# reverb2.net
KiCad netlist of a schematic drawn in EAGLE
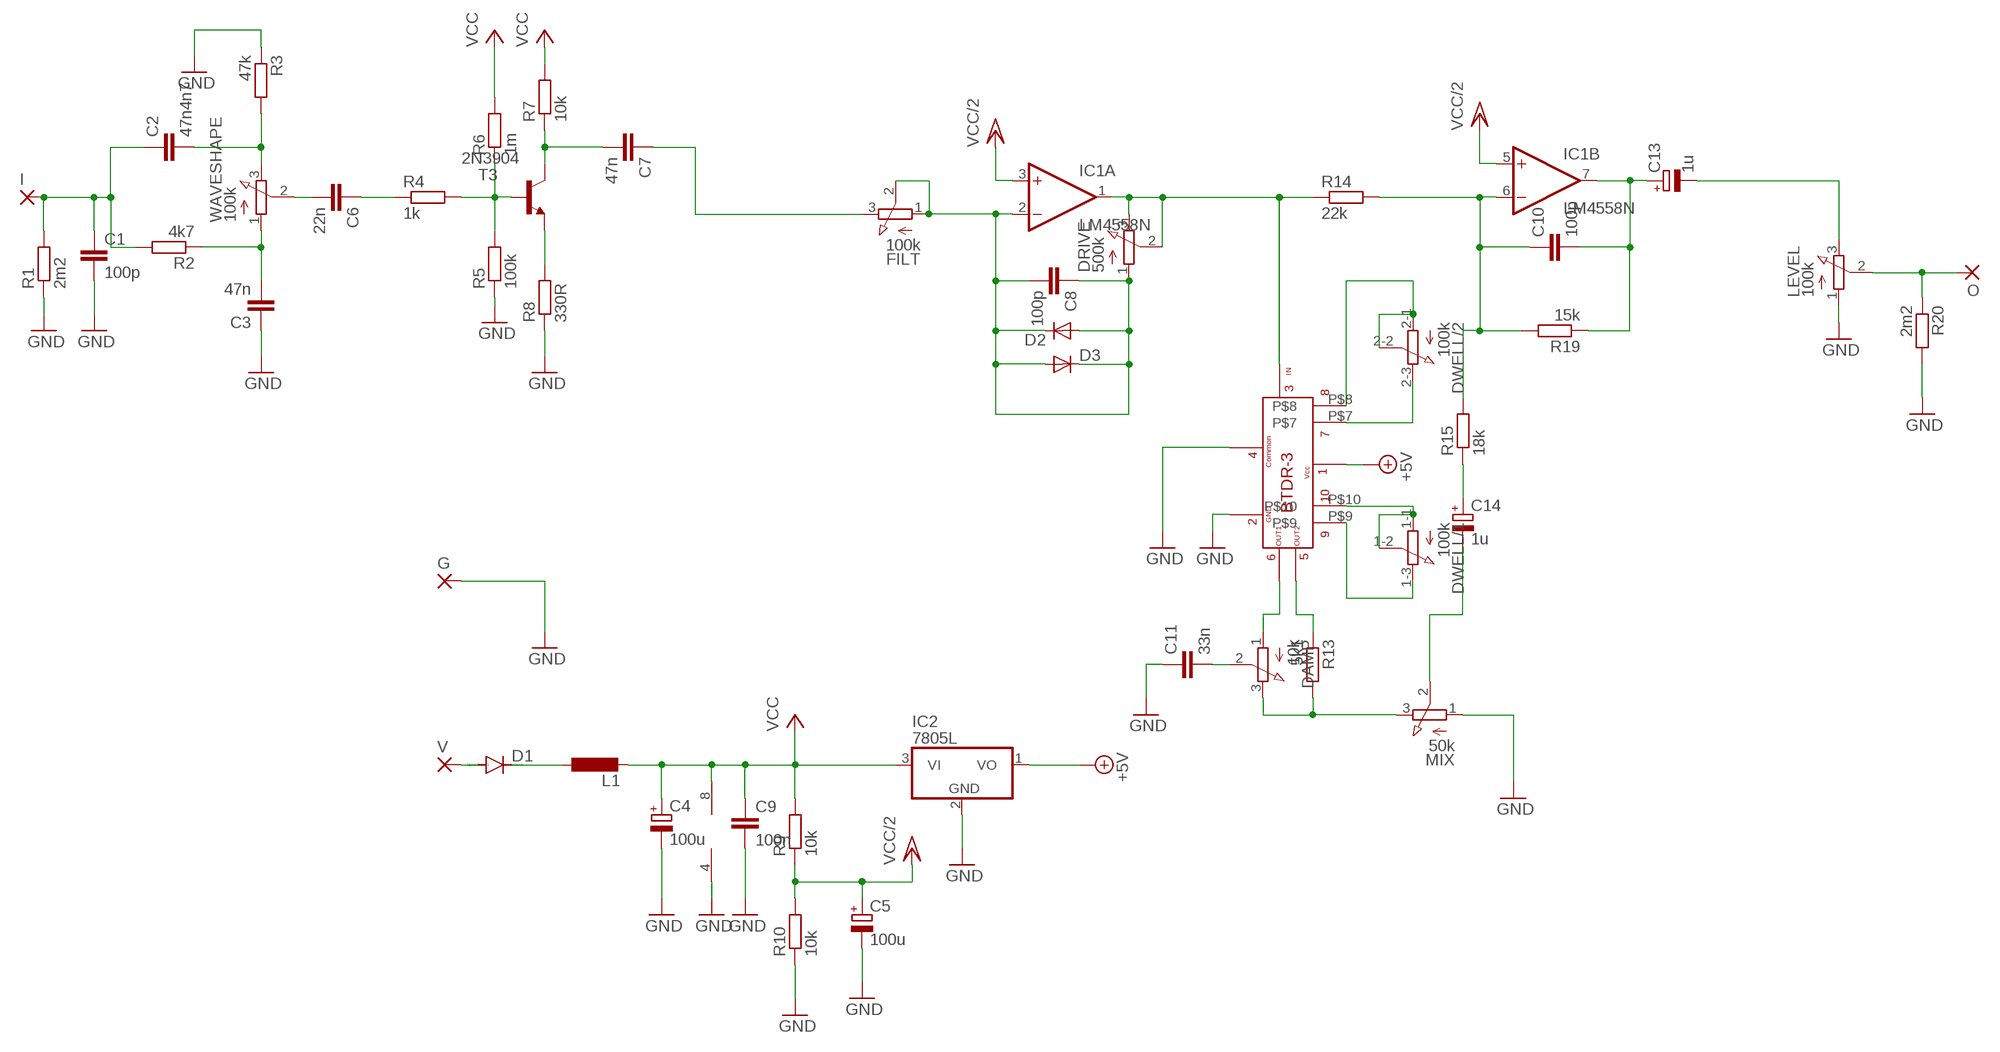
[diagram p0: schematic, sheet 1]

(export (version "E")
  (design (tool "Eeschema 10.0.6"))
  (components
    (comp (ref "C1")
      (value "100p")
      (footprint "eagle-import:S5MMHEXCAP")
      (libsource (lib "eagle-import") (part "C5/2.5"))
    )
    (comp (ref "C2")
      (value "47n4n7")
      (footprint "eagle-import:S5MMHEXCAP")
      (libsource (lib "eagle-import") (part "C5/2.5"))
    )
    (comp (ref "C3")
      (value "47n")
      (footprint "eagle-import:S5MMHEXCAP")
      (libsource (lib "eagle-import") (part "C5/2.5"))
    )
    (comp (ref "C4")
      (value "100u")
      (footprint "eagle-import:E2,5-7")
      (libsource (lib "eagle-import") (part "CPOL-EUE2.5-7"))
    )
    (comp (ref "C5")
      (value "100u")
      (footprint "eagle-import:E2,5-7")
      (libsource (lib "eagle-import") (part "CPOL-EUE2.5-7"))
    )
    (comp (ref "C6")
      (value "22n")
      (footprint "eagle-import:S5MMHEXCAP")
      (libsource (lib "eagle-import") (part "C5/2.5"))
    )
    (comp (ref "C7")
      (value "47n")
      (footprint "eagle-import:S5MMHEXCAP")
      (libsource (lib "eagle-import") (part "C5/2.5"))
    )
    (comp (ref "C8")
      (value "100p")
      (footprint "eagle-import:S5MMHEXCAP")
      (libsource (lib "eagle-import") (part "C5/2.5"))
    )
    (comp (ref "C9")
      (value "100n")
      (footprint "eagle-import:S5MMHEXCAP")
      (libsource (lib "eagle-import") (part "C5/2.5"))
    )
    (comp (ref "C10")
      (value "100p")
      (footprint "eagle-import:S5MMHEXCAP")
      (libsource (lib "eagle-import") (part "C5/2.5"))
    )
    (comp (ref "C11")
      (value "33n")
      (footprint "eagle-import:S5MMHEXCAP")
      (libsource (lib "eagle-import") (part "C5/2.5"))
    )
    (comp (ref "C13")
      (value "1u")
      (footprint "eagle-import:E2-4")
      (libsource (lib "eagle-import") (part "CPOL-EUE2-4"))
    )
    (comp (ref "C14")
      (value "1u")
      (footprint "eagle-import:E2-4")
      (libsource (lib "eagle-import") (part "CPOL-EUE2-4"))
    )
    (comp (ref "D1")
      (value "1N4148DO35-7")
      (footprint "eagle-import:DO35-7")
      (libsource (lib "eagle-import") (part "1N4148DO35-7"))
    )
    (comp (ref "D2")
      (value "SMALL_DIODEDO35-7")
      (footprint "eagle-import:DO35-7")
      (libsource (lib "eagle-import") (part "SMALL_DIODEDO35-7"))
    )
    (comp (ref "D3")
      (value "SMALL_DIODEDO35-7")
      (footprint "eagle-import:DO35-7")
      (libsource (lib "eagle-import") (part "SMALL_DIODEDO35-7"))
    )
    (comp (ref "DAMP")
      (value "10k")
      (footprint "eagle-import:3RP_1610N")
      (libsource (lib "eagle-import") (part "HEXPOT1"))
    )
    (comp (ref "DRIVE")
      (value "500k")
      (footprint "eagle-import:3RP_1610N")
      (libsource (lib "eagle-import") (part "HEXPOT1"))
    )
    (comp (ref "DWELL")
      (value "100k")
      (footprint "eagle-import:3RP_1610G")
      (libsource (lib "eagle-import") (part "3RP/1610G"))
    )
    (comp (ref "FILT")
      (value "100k")
      (footprint "eagle-import:3RP_1610N")
      (libsource (lib "eagle-import") (part "HEXPOT1"))
    )
    (comp (ref "G")
      (value "WIREPAD1,6/0,9")
      (footprint "eagle-import:1,6_0,9")
      (libsource (lib "eagle-import") (part "WIREPAD1,6/0,9"))
    )
    (comp (ref "I")
      (value "WIREPAD1,6/0,9")
      (footprint "eagle-import:1,6_0,9")
      (libsource (lib "eagle-import") (part "WIREPAD1,6/0,9"))
    )
    (comp (ref "IC1")
      (value "LM4558N")
      (footprint "eagle-import:DIL08")
      (libsource (lib "eagle-import") (part "4558NLM"))
    )
    (comp (ref "IC2")
      (value "7805L")
      (footprint "eagle-import:TO92")
      (libsource (lib "eagle-import") (part "78L05"))
    )
    (comp (ref "L1")
      (value "L-EU0204/7")
      (footprint "eagle-import:0204_7")
      (libsource (lib "eagle-import") (part "L-EU0204/7"))
    )
    (comp (ref "LEVEL")
      (value "100k")
      (footprint "eagle-import:3RP_1610N")
      (libsource (lib "eagle-import") (part "HEXPOT1"))
    )
    (comp (ref "MIX")
      (value "50k")
      (footprint "eagle-import:3RP_1610N")
      (libsource (lib "eagle-import") (part "HEXPOT1"))
    )
    (comp (ref "O")
      (value "WIREPAD1,6/0,9")
      (footprint "eagle-import:1,6_0,9")
      (libsource (lib "eagle-import") (part "WIREPAD1,6/0,9"))
    )
    (comp (ref "R1")
      (value "2m2")
      (footprint "eagle-import:0207_7")
      (libsource (lib "eagle-import") (part "R-EU_0207/7"))
    )
    (comp (ref "R2")
      (value "4k7")
      (footprint "eagle-import:0207_7")
      (libsource (lib "eagle-import") (part "R-EU_0207/7"))
    )
    (comp (ref "R3")
      (value "47k")
      (footprint "eagle-import:0207_7")
      (libsource (lib "eagle-import") (part "R-EU_0207/7"))
    )
    (comp (ref "R4")
      (value "1k")
      (footprint "eagle-import:0207_7")
      (libsource (lib "eagle-import") (part "R-EU_0207/7"))
    )
    (comp (ref "R5")
      (value "100k")
      (footprint "eagle-import:0207_7")
      (libsource (lib "eagle-import") (part "R-EU_0207/7"))
    )
    (comp (ref "R6")
      (value "1m")
      (footprint "eagle-import:0207_7")
      (libsource (lib "eagle-import") (part "R-EU_0207/7"))
    )
    (comp (ref "R7")
      (value "10k")
      (footprint "eagle-import:0207_7")
      (libsource (lib "eagle-import") (part "R-EU_0207/7"))
    )
    (comp (ref "R8")
      (value "330R")
      (footprint "eagle-import:0207_7")
      (libsource (lib "eagle-import") (part "R-EU_0207/7"))
    )
    (comp (ref "R9")
      (value "10k")
      (footprint "eagle-import:0207_7")
      (libsource (lib "eagle-import") (part "R-EU_0207/7"))
    )
    (comp (ref "R10")
      (value "10k")
      (footprint "eagle-import:0207_7")
      (libsource (lib "eagle-import") (part "R-EU_0207/7"))
    )
    (comp (ref "R13")
      (value "5k1")
      (footprint "eagle-import:0207_7")
      (libsource (lib "eagle-import") (part "R-EU_0207/7"))
    )
    (comp (ref "R14")
      (value "22k")
      (footprint "eagle-import:0207_7")
      (libsource (lib "eagle-import") (part "R-EU_0207/7"))
    )
    (comp (ref "R15")
      (value "18k")
      (footprint "eagle-import:0207_7")
      (libsource (lib "eagle-import") (part "R-EU_0207/7"))
    )
    (comp (ref "R19")
      (value "15k")
      (footprint "eagle-import:0207_7")
      (libsource (lib "eagle-import") (part "R-EU_0207/7"))
    )
    (comp (ref "R20")
      (value "2m2")
      (footprint "eagle-import:0207_7")
      (libsource (lib "eagle-import") (part "R-EU_0207/7"))
    )
    (comp (ref "T3")
      (value "2N3904")
      (footprint "eagle-import:TO92")
      (libsource (lib "eagle-import") (part "2N3904"))
    )
    (comp (ref "U$2")
      (value "BTDR-3")
      (footprint "eagle-import:BTDR3")
      (libsource (lib "eagle-import") (part "BTDR-3"))
    )
    (comp (ref "V")
      (value "WIREPAD1,6/0,9")
      (footprint "eagle-import:1,6_0,9")
      (libsource (lib "eagle-import") (part "WIREPAD1,6/0,9"))
    )
    (comp (ref "WAVESHAPE")
      (value "100k")
      (footprint "eagle-import:3RP_1610N")
      (libsource (lib "eagle-import") (part "HEXPOT1"))
    )
  )
  (nets
    (net (code "1") (name "+5V") (class "Default")
      (node (ref "IC2") (pin "1") (pinfunction "VO_1") (pintype "passive"))
      (node (ref "U$2") (pin "P$1") (pinfunction "P$1_P$1") (pintype "bidirectional"))
    )
    (net (code "2") (name "GND") (class "Default")
      (node (ref "C1") (pin "2") (pinfunction "2_2") (pintype "passive"))
      (node (ref "C11") (pin "1") (pinfunction "1_1") (pintype "passive"))
      (node (ref "C3") (pin "1") (pinfunction "1_1") (pintype "passive"))
      (node (ref "C4") (pin "-") (pinfunction "-_-") (pintype "passive"))
      (node (ref "C5") (pin "-") (pinfunction "-_-") (pintype "passive"))
      (node (ref "C9") (pin "2") (pinfunction "2_2") (pintype "passive"))
      (node (ref "G") (pin "1") (pinfunction "P_1") (pintype "passive"))
      (node (ref "IC1") (pin "4") (pinfunction "V-_4") (pintype "power_in"))
      (node (ref "IC2") (pin "2") (pinfunction "GND_2") (pintype "passive"))
      (node (ref "LEVEL") (pin "1") (pinfunction "A_1") (pintype "passive"))
      (node (ref "MIX") (pin "1") (pinfunction "A_1") (pintype "passive"))
      (node (ref "R1") (pin "1") (pinfunction "1_1") (pintype "passive"))
      (node (ref "R10") (pin "1") (pinfunction "1_1") (pintype "passive"))
      (node (ref "R20") (pin "2") (pinfunction "2_2") (pintype "passive"))
      (node (ref "R3") (pin "1") (pinfunction "1_1") (pintype "passive"))
      (node (ref "R5") (pin "1") (pinfunction "1_1") (pintype "passive"))
      (node (ref "R8") (pin "1") (pinfunction "1_1") (pintype "passive"))
      (node (ref "U$2") (pin "P$2") (pinfunction "P$2_P$2") (pintype "bidirectional"))
      (node (ref "U$2") (pin "P$4") (pinfunction "P$4_P$4") (pintype "bidirectional"))
    )
    (net (code "3") (name "Net-(C6-Pad1)") (class "Default")
      (node (ref "C6") (pin "1") (pinfunction "1_1") (pintype "passive"))
      (node (ref "R4") (pin "1") (pinfunction "1_1") (pintype "passive"))
    )
    (net (code "4") (name "Net-(C14-Pad+)") (class "Default")
      (node (ref "C14") (pin "+") (pinfunction "+_+") (pintype "passive"))
      (node (ref "R15") (pin "1") (pinfunction "1_1") (pintype "passive"))
    )
    (net (code "5") (name "Net-(D1-PadC)") (class "Default")
      (node (ref "D1") (pin "C") (pinfunction "C_C") (pintype "passive"))
      (node (ref "L1") (pin "1") (pinfunction "1_1") (pintype "passive"))
    )
    (net (code "6") (name "Net-(DAMP-A)") (class "Default")
      (node (ref "DAMP") (pin "1") (pinfunction "A_1") (pintype "passive"))
      (node (ref "U$2") (pin "P$6") (pinfunction "P$6_P$6") (pintype "bidirectional"))
    )
    (net (code "7") (name "Net-(DAMP-E)") (class "Default")
      (node (ref "DAMP") (pin "3") (pinfunction "E_3") (pintype "passive"))
      (node (ref "MIX") (pin "3") (pinfunction "E_3") (pintype "passive"))
      (node (ref "R13") (pin "2") (pinfunction "2_2") (pintype "passive"))
    )
    (net (code "8") (name "Net-(DAMP-S)") (class "Default")
      (node (ref "C11") (pin "2") (pinfunction "2_2") (pintype "passive"))
      (node (ref "DAMP") (pin "2") (pinfunction "S_2") (pintype "passive"))
    )
    (net (code "9") (name "Net-(DRIVE-A)") (class "Default")
      (node (ref "C8") (pin "1") (pinfunction "1_1") (pintype "passive"))
      (node (ref "C8") (pin "2") (pinfunction "2_2") (pintype "passive"))
      (node (ref "D2") (pin "A") (pinfunction "A_A") (pintype "passive"))
      (node (ref "D2") (pin "C") (pinfunction "C_C") (pintype "passive"))
      (node (ref "D3") (pin "A") (pinfunction "A_A") (pintype "passive"))
      (node (ref "D3") (pin "C") (pinfunction "C_C") (pintype "passive"))
      (node (ref "DRIVE") (pin "1") (pinfunction "A_1") (pintype "passive"))
      (node (ref "FILT") (pin "1") (pinfunction "A_1") (pintype "passive"))
      (node (ref "FILT") (pin "2") (pinfunction "S_2") (pintype "passive"))
      (node (ref "IC1") (pin "2") (pinfunction "-IN_2") (pintype "input"))
    )
    (net (code "10") (name "Net-(DRIVE-E)") (class "Default")
      (node (ref "DRIVE") (pin "2") (pinfunction "S_2") (pintype "passive"))
      (node (ref "DRIVE") (pin "3") (pinfunction "E_3") (pintype "passive"))
      (node (ref "IC1") (pin "1") (pinfunction "OUT_1") (pintype "output"))
      (node (ref "R14") (pin "1") (pinfunction "1_1") (pintype "passive"))
      (node (ref "U$2") (pin "P$3") (pinfunction "P$3_P$3") (pintype "bidirectional"))
    )
    (net (code "11") (name "Net-(DWELLA-A)") (class "Default")
      (node (ref "DWELL") (pin "1-1") (pinfunction "A_1-1") (pintype "passive"))
      (node (ref "DWELL") (pin "1-2") (pinfunction "S_1-2") (pintype "passive"))
      (node (ref "U$2") (pin "P$10") (pinfunction "P$10_P$10") (pintype "bidirectional"))
    )
    (net (code "12") (name "Net-(DWELLA-E)") (class "Default")
      (node (ref "DWELL") (pin "1-3") (pinfunction "E_1-3") (pintype "passive"))
      (node (ref "U$2") (pin "P$9") (pinfunction "P$9_P$9") (pintype "bidirectional"))
    )
    (net (code "13") (name "Net-(DWELLB-A)") (class "Default")
      (node (ref "DWELL") (pin "2-1") (pinfunction "A_2-1") (pintype "passive"))
      (node (ref "DWELL") (pin "2-2") (pinfunction "S_2-2") (pintype "passive"))
      (node (ref "U$2") (pin "P$8") (pinfunction "P$8_P$8") (pintype "bidirectional"))
    )
    (net (code "14") (name "Net-(DWELLB-E)") (class "Default")
      (node (ref "DWELL") (pin "2-3") (pinfunction "E_2-3") (pintype "passive"))
      (node (ref "U$2") (pin "P$7") (pinfunction "P$7_P$7") (pintype "bidirectional"))
    )
    (net (code "15") (name "Net-(FILT-E)") (class "Default")
      (node (ref "C7") (pin "1") (pinfunction "1_1") (pintype "passive"))
      (node (ref "FILT") (pin "3") (pinfunction "E_3") (pintype "passive"))
    )
    (net (code "16") (name "Net-(I-P)") (class "Default")
      (node (ref "C1") (pin "1") (pinfunction "1_1") (pintype "passive"))
      (node (ref "C2") (pin "1") (pinfunction "1_1") (pintype "passive"))
      (node (ref "I") (pin "1") (pinfunction "P_1") (pintype "passive"))
      (node (ref "R1") (pin "2") (pinfunction "2_2") (pintype "passive"))
      (node (ref "R2") (pin "2") (pinfunction "2_2") (pintype "passive"))
    )
    (net (code "17") (name "Net-(IC1B--IN)") (class "Default")
      (node (ref "C10") (pin "1") (pinfunction "1_1") (pintype "passive"))
      (node (ref "IC1") (pin "6") (pinfunction "-IN_6") (pintype "input"))
      (node (ref "R14") (pin "2") (pinfunction "2_2") (pintype "passive"))
      (node (ref "R15") (pin "2") (pinfunction "2_2") (pintype "passive"))
      (node (ref "R19") (pin "2") (pinfunction "2_2") (pintype "passive"))
    )
    (net (code "18") (name "Net-(IC1B-OUT)") (class "Default")
      (node (ref "C10") (pin "2") (pinfunction "2_2") (pintype "passive"))
      (node (ref "C13") (pin "+") (pinfunction "+_+") (pintype "passive"))
      (node (ref "IC1") (pin "7") (pinfunction "OUT_7") (pintype "output"))
      (node (ref "R19") (pin "1") (pinfunction "1_1") (pintype "passive"))
    )
    (net (code "19") (name "Net-(LEVEL-E)") (class "Default")
      (node (ref "C13") (pin "-") (pinfunction "-_-") (pintype "passive"))
      (node (ref "LEVEL") (pin "3") (pinfunction "E_3") (pintype "passive"))
    )
    (net (code "20") (name "Net-(LEVEL-S)") (class "Default")
      (node (ref "LEVEL") (pin "2") (pinfunction "S_2") (pintype "passive"))
      (node (ref "O") (pin "1") (pinfunction "P_1") (pintype "passive"))
      (node (ref "R20") (pin "1") (pinfunction "1_1") (pintype "passive"))
    )
    (net (code "21") (name "Net-(MIX-S)") (class "Default")
      (node (ref "C14") (pin "-") (pinfunction "-_-") (pintype "passive"))
      (node (ref "MIX") (pin "2") (pinfunction "S_2") (pintype "passive"))
    )
    (net (code "22") (name "Net-(R13-Pad1)") (class "Default")
      (node (ref "R13") (pin "1") (pinfunction "1_1") (pintype "passive"))
      (node (ref "U$2") (pin "P$5") (pinfunction "P$5_P$5") (pintype "bidirectional"))
    )
    (net (code "23") (name "Net-(T3-B)") (class "Default")
      (node (ref "R4") (pin "2") (pinfunction "2_2") (pintype "passive"))
      (node (ref "R5") (pin "2") (pinfunction "2_2") (pintype "passive"))
      (node (ref "R6") (pin "1") (pinfunction "1_1") (pintype "passive"))
      (node (ref "T3") (pin "2") (pinfunction "B_2") (pintype "passive"))
    )
    (net (code "24") (name "Net-(T3-C)") (class "Default")
      (node (ref "C7") (pin "2") (pinfunction "2_2") (pintype "passive"))
      (node (ref "R7") (pin "1") (pinfunction "1_1") (pintype "passive"))
      (node (ref "T3") (pin "1") (pinfunction "C_1") (pintype "passive"))
    )
    (net (code "25") (name "Net-(T3-E)") (class "Default")
      (node (ref "R8") (pin "2") (pinfunction "2_2") (pintype "passive"))
      (node (ref "T3") (pin "3") (pinfunction "E_3") (pintype "passive"))
    )
    (net (code "26") (name "Net-(V-P)") (class "Default")
      (node (ref "D1") (pin "A") (pinfunction "A_A") (pintype "passive"))
      (node (ref "V") (pin "1") (pinfunction "P_1") (pintype "passive"))
    )
    (net (code "27") (name "Net-(WAVESHAPE-A)") (class "Default")
      (node (ref "C3") (pin "2") (pinfunction "2_2") (pintype "passive"))
      (node (ref "R2") (pin "1") (pinfunction "1_1") (pintype "passive"))
      (node (ref "WAVESHAPE") (pin "1") (pinfunction "A_1") (pintype "passive"))
    )
    (net (code "28") (name "Net-(WAVESHAPE-E)") (class "Default")
      (node (ref "C2") (pin "2") (pinfunction "2_2") (pintype "passive"))
      (node (ref "R3") (pin "2") (pinfunction "2_2") (pintype "passive"))
      (node (ref "WAVESHAPE") (pin "3") (pinfunction "E_3") (pintype "passive"))
    )
    (net (code "29") (name "Net-(WAVESHAPE-S)") (class "Default")
      (node (ref "C6") (pin "2") (pinfunction "2_2") (pintype "passive"))
      (node (ref "WAVESHAPE") (pin "2") (pinfunction "S_2") (pintype "passive"))
    )
    (net (code "30") (name "VCC") (class "Default")
      (node (ref "C4") (pin "+") (pinfunction "+_+") (pintype "passive"))
      (node (ref "C9") (pin "1") (pinfunction "1_1") (pintype "passive"))
      (node (ref "IC1") (pin "8") (pinfunction "V+_8") (pintype "power_in"))
      (node (ref "IC2") (pin "3") (pinfunction "VI_3") (pintype "input"))
      (node (ref "L1") (pin "2") (pinfunction "2_2") (pintype "passive"))
      (node (ref "R6") (pin "2") (pinfunction "2_2") (pintype "passive"))
      (node (ref "R7") (pin "2") (pinfunction "2_2") (pintype "passive"))
      (node (ref "R9") (pin "2") (pinfunction "2_2") (pintype "passive"))
    )
    (net (code "31") (name "VCC{slash}2") (class "Default")
      (node (ref "C5") (pin "+") (pinfunction "+_+") (pintype "passive"))
      (node (ref "IC1") (pin "3") (pinfunction "+IN_3") (pintype "input"))
      (node (ref "IC1") (pin "5") (pinfunction "+IN_5") (pintype "input"))
      (node (ref "R10") (pin "2") (pinfunction "2_2") (pintype "passive"))
      (node (ref "R9") (pin "1") (pinfunction "1_1") (pintype "passive"))
    )
  )
)
